# schematic.net
KiCad netlist of a schematic drawn in EAGLE
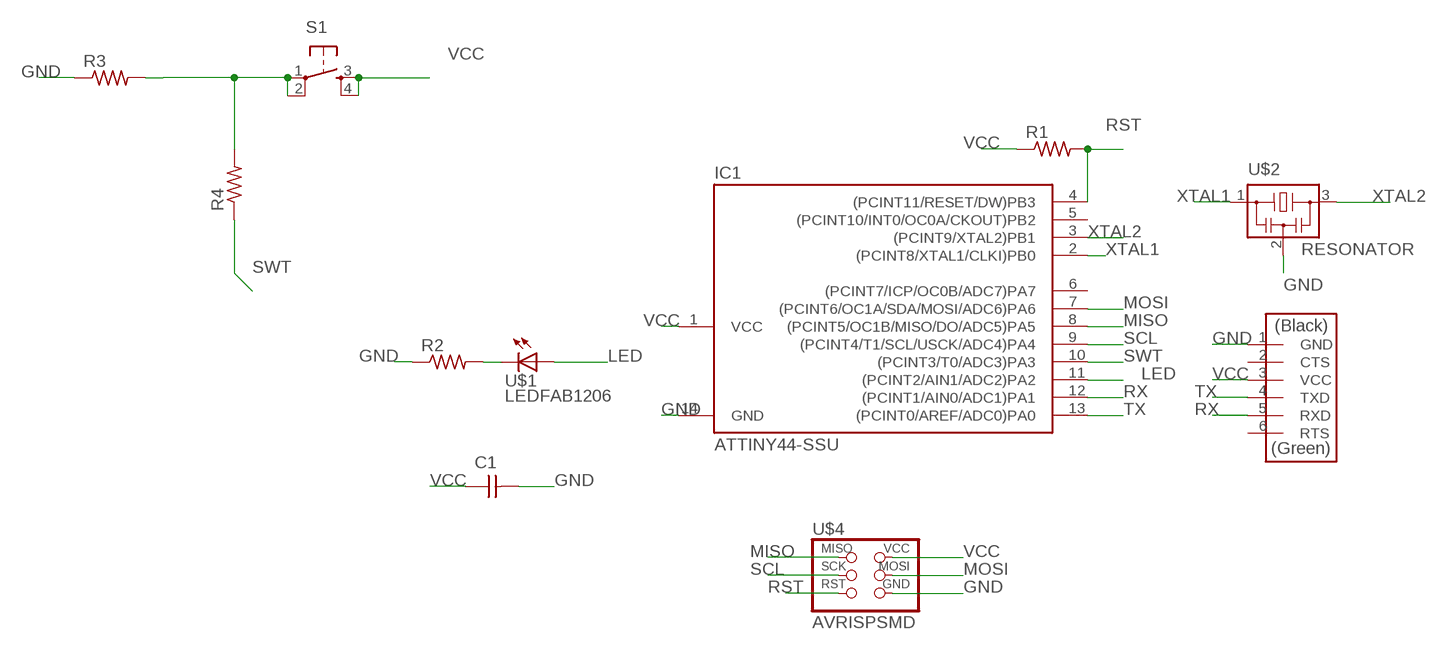
[diagram p0: schematic, sheet 1]

(export (version "E")
  (design (tool "Eeschema 10.0.6"))
  (components
    (comp (ref "C1")
      (value "CAP-UNPOLARIZEDFAB")
      (footprint "eagle-import:C1206FAB")
      (libsource (lib "eagle-import") (part "CAP-UNPOLARIZEDFAB"))
    )
    (comp (ref "IC1")
      (value "ATTINY44-SSU")
      (footprint "eagle-import:SOIC14")
      (libsource (lib "eagle-import") (part "ATTINY44-SSU"))
    )
    (comp (ref "R1")
      (value "RES-US1206FAB")
      (footprint "eagle-import:R1206FAB")
      (libsource (lib "eagle-import") (part "RES-US1206FAB"))
    )
    (comp (ref "R2")
      (value "RES-US1206FAB")
      (footprint "eagle-import:R1206FAB")
      (libsource (lib "eagle-import") (part "RES-US1206FAB"))
    )
    (comp (ref "R3")
      (value "RES-US1206FAB")
      (footprint "eagle-import:R1206FAB")
      (libsource (lib "eagle-import") (part "RES-US1206FAB"))
    )
    (comp (ref "R4")
      (value "RES-US1206FAB")
      (footprint "eagle-import:R1206FAB")
      (libsource (lib "eagle-import") (part "RES-US1206FAB"))
    )
    (comp (ref "S1")
      (value "6MM_SWITCH6MM_SWITCH")
      (footprint "eagle-import:6MM_SWITCH")
      (libsource (lib "eagle-import") (part "6MM_SWITCH6MM_SWITCH"))
    )
    (comp (ref "U$1")
      (value "LEDFAB1206")
      (footprint "eagle-import:LED1206FAB")
      (libsource (lib "eagle-import") (part "LEDFAB1206"))
    )
    (comp (ref "U$2")
      (value "RESONATOR")
      (footprint "eagle-import:EFOBM")
      (libsource (lib "eagle-import") (part "RESONATOR"))
    )
    (comp (ref "U$3")
      (value "FTDI-SMD-HEADER")
      (footprint "eagle-import:1X06SMD")
      (libsource (lib "eagle-import") (part "FTDI-SMD-HEADER"))
    )
    (comp (ref "U$4")
      (value "AVRISPSMD")
      (footprint "eagle-import:2X03SMD")
      (libsource (lib "eagle-import") (part "AVRISPSMD"))
    )
  )
  (nets
    (net (code "1") (name "/GND") (class "Default")
      (node (ref "C1") (pin "2") (pinfunction "2_2") (pintype "passive"))
      (node (ref "IC1") (pin "14") (pinfunction "GND_14") (pintype "power_in"))
      (node (ref "R2") (pin "1") (pinfunction "1_1") (pintype "passive"))
      (node (ref "R3") (pin "1") (pinfunction "1_1") (pintype "passive"))
      (node (ref "U$2") (pin "2") (pinfunction "2_2") (pintype "passive"))
      (node (ref "U$3") (pin "1") (pinfunction "GND_1") (pintype "bidirectional"))
      (node (ref "U$4") (pin "6") (pinfunction "GND_6") (pintype "passive"))
    )
    (net (code "2") (name "/LED") (class "Default")
      (node (ref "IC1") (pin "11") (pinfunction "(PCINT2/AIN1/ADC2)PA2_11") (pintype "bidirectional"))
      (node (ref "U$1") (pin "1") (pinfunction "A_1") (pintype "passive"))
    )
    (net (code "3") (name "/MISO") (class "Default")
      (node (ref "IC1") (pin "8") (pinfunction "(PCINT5/OC1B/MISO/DO/ADC5)PA5_8") (pintype "bidirectional"))
      (node (ref "U$4") (pin "1") (pinfunction "MISO_1") (pintype "passive"))
    )
    (net (code "4") (name "/MOSI") (class "Default")
      (node (ref "IC1") (pin "7") (pinfunction "(PCINT6/OC1A/SDA/MOSI/ADC6)PA6_7") (pintype "bidirectional"))
      (node (ref "U$4") (pin "4") (pinfunction "MOSI_4") (pintype "passive"))
    )
    (net (code "5") (name "/RST") (class "Default")
      (node (ref "IC1") (pin "4") (pinfunction "(PCINT11/RESET/DW)PB3_4") (pintype "bidirectional"))
      (node (ref "R1") (pin "2") (pinfunction "2_2") (pintype "passive"))
      (node (ref "U$4") (pin "5") (pinfunction "RST_5") (pintype "passive"))
    )
    (net (code "6") (name "/RX") (class "Default")
      (node (ref "IC1") (pin "12") (pinfunction "(PCINT1/AIN0/ADC1)PA1_12") (pintype "bidirectional"))
      (node (ref "U$3") (pin "5") (pinfunction "RXD_5") (pintype "bidirectional"))
    )
    (net (code "7") (name "/SCL") (class "Default")
      (node (ref "IC1") (pin "9") (pinfunction "(PCINT4/T1/SCL/USCK/ADC4)PA4_9") (pintype "bidirectional"))
      (node (ref "U$4") (pin "3") (pinfunction "SCK_3") (pintype "passive"))
    )
    (net (code "8") (name "/SWT") (class "Default")
      (node (ref "IC1") (pin "10") (pinfunction "(PCINT3/T0/ADC3)PA3_10") (pintype "bidirectional"))
      (node (ref "R4") (pin "1") (pinfunction "1_1") (pintype "passive"))
    )
    (net (code "9") (name "/TX") (class "Default")
      (node (ref "IC1") (pin "13") (pinfunction "(PCINT0/AREF/ADC0)PA0_13") (pintype "bidirectional"))
      (node (ref "U$3") (pin "4") (pinfunction "TXD_4") (pintype "bidirectional"))
    )
    (net (code "10") (name "/VCC") (class "Default")
      (node (ref "C1") (pin "1") (pinfunction "1_1") (pintype "passive"))
      (node (ref "IC1") (pin "1") (pinfunction "VCC_1") (pintype "power_in"))
      (node (ref "R1") (pin "1") (pinfunction "1_1") (pintype "passive"))
      (node (ref "S1") (pin "3") (pinfunction "S_3") (pintype "passive"))
      (node (ref "S1") (pin "4") (pinfunction "S1_4") (pintype "passive"))
      (node (ref "U$3") (pin "3") (pinfunction "VCC_3") (pintype "bidirectional"))
      (node (ref "U$4") (pin "2") (pinfunction "VCC_2") (pintype "passive"))
    )
    (net (code "11") (name "/XTAL1") (class "Default")
      (node (ref "IC1") (pin "2") (pinfunction "(PCINT8/XTAL1/CLKI)PB0_2") (pintype "bidirectional"))
      (node (ref "U$2") (pin "1") (pinfunction "1_1") (pintype "passive"))
    )
    (net (code "12") (name "/XTAL2") (class "Default")
      (node (ref "IC1") (pin "3") (pinfunction "(PCINT9/XTAL2)PB1_3") (pintype "bidirectional"))
      (node (ref "U$2") (pin "3") (pinfunction "3_3") (pintype "passive"))
    )
    (net (code "13") (name "Net-(S1-P)") (class "Default")
      (node (ref "R3") (pin "2") (pinfunction "2_2") (pintype "passive"))
      (node (ref "R4") (pin "2") (pinfunction "2_2") (pintype "passive"))
      (node (ref "S1") (pin "1") (pinfunction "P_1") (pintype "passive"))
      (node (ref "S1") (pin "2") (pinfunction "P1_2") (pintype "passive"))
    )
    (net (code "14") (name "Net-(U$1-C)") (class "Default")
      (node (ref "R2") (pin "2") (pinfunction "2_2") (pintype "passive"))
      (node (ref "U$1") (pin "2") (pinfunction "C_2") (pintype "passive"))
    )
    (net (code "15") (name "unconnected-(IC1-(PCINT7{slash}ICP{slash}OC0B{slash}ADC7)PA7-Pad6)") (class "Default")
      (node (ref "IC1") (pin "6") (pinfunction "(PCINT7/ICP/OC0B/ADC7)PA7_6") (pintype "bidirectional"))
    )
    (net (code "16") (name "unconnected-(IC1-(PCINT10{slash}INT0{slash}OC0A{slash}CKOUT)PB2-Pad5)") (class "Default")
      (node (ref "IC1") (pin "5") (pinfunction "(PCINT10/INT0/OC0A/CKOUT)PB2_5") (pintype "bidirectional"))
    )
    (net (code "17") (name "unconnected-(U$3-CTS-Pad2)") (class "Default")
      (node (ref "U$3") (pin "2") (pinfunction "CTS_2") (pintype "bidirectional"))
    )
    (net (code "18") (name "unconnected-(U$3-RTS-Pad6)") (class "Default")
      (node (ref "U$3") (pin "6") (pinfunction "RTS_6") (pintype "bidirectional"))
    )
  )
)
